# ESP32-ng.net
KiCad netlist of a schematic drawn in EAGLE
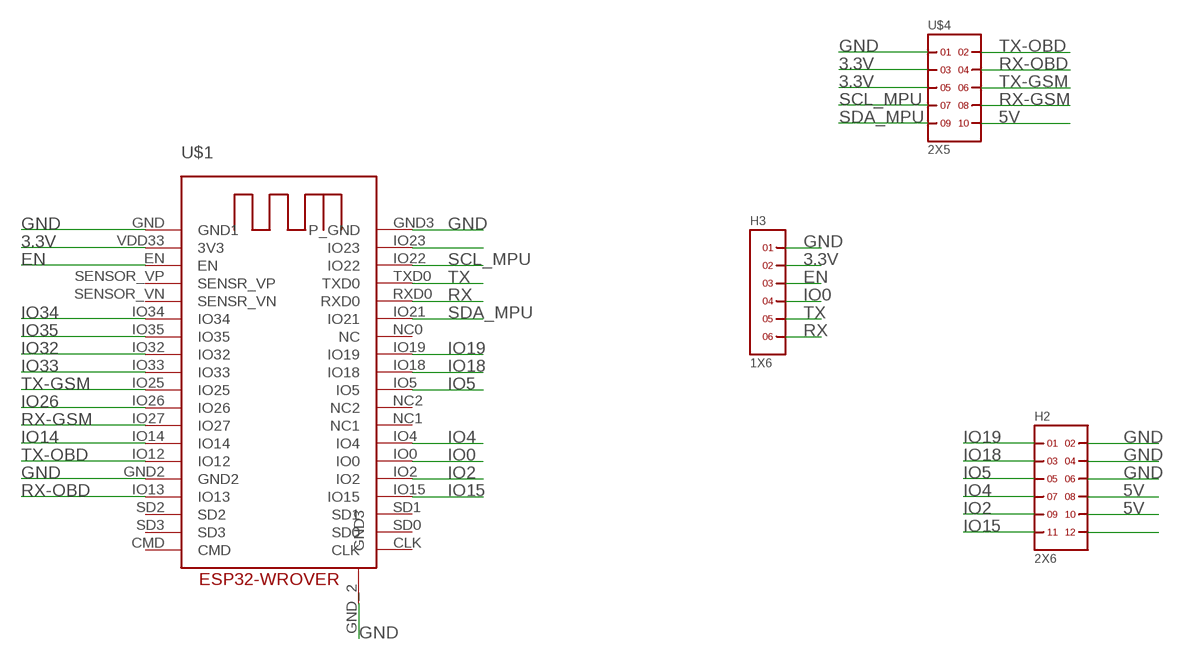
[diagram p0: schematic, sheet 1]

(export (version "E")
  (design (tool "Eeschema 10.0.6"))
  (components
    (comp (ref "H2")
      (value "2X6")
      (footprint "eagle-import:2X6")
      (libsource (lib "eagle-import") (part "2X6"))
    )
    (comp (ref "H3")
      (value "1X6")
      (footprint "eagle-import:1X6")
      (libsource (lib "eagle-import") (part "1X6"))
    )
    (comp (ref "U$1")
      (value "ESP32-WROVER")
      (footprint "eagle-import:ESP32-WROVER")
      (libsource (lib "eagle-import") (part "ESP32-WROVER"))
    )
    (comp (ref "U$4")
      (value "2X5")
      (footprint "eagle-import:2X5")
      (libsource (lib "eagle-import") (part "2X5"))
    )
  )
  (nets
    (net (code "1") (name "/3.3V") (class "Default")
      (node (ref "H3") (pin "2") (pinfunction "2_2") (pintype "bidirectional"))
      (node (ref "U$1") (pin "VDD33") (pinfunction "3V3_VDD33") (pintype "bidirectional"))
      (node (ref "U$4") (pin "3") (pinfunction "3_3") (pintype "bidirectional"))
      (node (ref "U$4") (pin "5") (pinfunction "5_5") (pintype "bidirectional"))
    )
    (net (code "2") (name "/5V") (class "Default")
      (node (ref "H2") (pin "10") (pinfunction "10_10") (pintype "bidirectional"))
      (node (ref "H2") (pin "8") (pinfunction "8_8") (pintype "bidirectional"))
      (node (ref "U$4") (pin "10") (pinfunction "10_10") (pintype "bidirectional"))
    )
    (net (code "3") (name "/EN") (class "Default")
      (node (ref "H3") (pin "3") (pinfunction "3_3") (pintype "bidirectional"))
      (node (ref "U$1") (pin "EN") (pinfunction "EN_EN") (pintype "bidirectional"))
    )
    (net (code "4") (name "/GND") (class "Default")
      (node (ref "H2") (pin "2") (pinfunction "2_2") (pintype "bidirectional"))
      (node (ref "H2") (pin "4") (pinfunction "4_4") (pintype "bidirectional"))
      (node (ref "H2") (pin "6") (pinfunction "6_6") (pintype "bidirectional"))
      (node (ref "H3") (pin "1") (pinfunction "1_1") (pintype "bidirectional"))
      (node (ref "U$1") (pin "GND") (pinfunction "GND1_GND") (pintype "bidirectional"))
      (node (ref "U$1") (pin "GND2") (pinfunction "GND2_GND2") (pintype "bidirectional"))
      (node (ref "U$1") (pin "GND3") (pinfunction "P_GND_GND3") (pintype "bidirectional"))
      (node (ref "U$1") (pin "GND_2") (pinfunction "GND3_GND_2") (pintype "bidirectional"))
      (node (ref "U$4") (pin "1") (pinfunction "1_1") (pintype "bidirectional"))
    )
    (net (code "5") (name "/IO0") (class "Default")
      (node (ref "H3") (pin "4") (pinfunction "4_4") (pintype "bidirectional"))
      (node (ref "U$1") (pin "IO0") (pinfunction "IO0_IO0") (pintype "bidirectional"))
    )
    (net (code "6") (name "/IO2") (class "Default")
      (node (ref "H2") (pin "9") (pinfunction "9_9") (pintype "bidirectional"))
      (node (ref "U$1") (pin "IO2") (pinfunction "IO2_IO2") (pintype "bidirectional"))
    )
    (net (code "7") (name "/IO4") (class "Default")
      (node (ref "H2") (pin "7") (pinfunction "7_7") (pintype "bidirectional"))
      (node (ref "U$1") (pin "IO4") (pinfunction "IO4_IO4") (pintype "bidirectional"))
    )
    (net (code "8") (name "/IO5") (class "Default")
      (node (ref "H2") (pin "5") (pinfunction "5_5") (pintype "bidirectional"))
      (node (ref "U$1") (pin "IO5") (pinfunction "IO5_IO5") (pintype "bidirectional"))
    )
    (net (code "9") (name "/IO14") (class "Default")
      (node (ref "U$1") (pin "IO14") (pinfunction "IO14_IO14") (pintype "bidirectional"))
    )
    (net (code "10") (name "/IO15") (class "Default")
      (node (ref "H2") (pin "11") (pinfunction "11_11") (pintype "bidirectional"))
      (node (ref "U$1") (pin "IO15") (pinfunction "IO15_IO15") (pintype "bidirectional"))
    )
    (net (code "11") (name "/IO18") (class "Default")
      (node (ref "H2") (pin "3") (pinfunction "3_3") (pintype "bidirectional"))
      (node (ref "U$1") (pin "IO18") (pinfunction "IO18_IO18") (pintype "bidirectional"))
    )
    (net (code "12") (name "/IO19") (class "Default")
      (node (ref "H2") (pin "1") (pinfunction "1_1") (pintype "bidirectional"))
      (node (ref "U$1") (pin "IO19") (pinfunction "IO19_IO19") (pintype "bidirectional"))
    )
    (net (code "13") (name "/IO26") (class "Default")
      (node (ref "U$1") (pin "IO26") (pinfunction "IO26_IO26") (pintype "bidirectional"))
    )
    (net (code "14") (name "/IO32") (class "Default")
      (node (ref "U$1") (pin "IO32") (pinfunction "IO32_IO32") (pintype "bidirectional"))
    )
    (net (code "15") (name "/IO33") (class "Default")
      (node (ref "U$1") (pin "IO33") (pinfunction "IO33_IO33") (pintype "bidirectional"))
    )
    (net (code "16") (name "/IO34") (class "Default")
      (node (ref "U$1") (pin "IO34") (pinfunction "IO34_IO34") (pintype "bidirectional"))
    )
    (net (code "17") (name "/IO35") (class "Default")
      (node (ref "U$1") (pin "IO35") (pinfunction "IO35_IO35") (pintype "bidirectional"))
    )
    (net (code "18") (name "/RX") (class "Default")
      (node (ref "H3") (pin "6") (pinfunction "6_6") (pintype "bidirectional"))
      (node (ref "U$1") (pin "RXD0") (pinfunction "RXD0_RXD0") (pintype "bidirectional"))
    )
    (net (code "19") (name "/RX-GSM") (class "Default")
      (node (ref "U$1") (pin "IO27") (pinfunction "IO27_IO27") (pintype "bidirectional"))
      (node (ref "U$4") (pin "8") (pinfunction "8_8") (pintype "bidirectional"))
    )
    (net (code "20") (name "/RX-OBD") (class "Default")
      (node (ref "U$1") (pin "IO13") (pinfunction "IO13_IO13") (pintype "bidirectional"))
      (node (ref "U$4") (pin "4") (pinfunction "4_4") (pintype "bidirectional"))
    )
    (net (code "21") (name "/SCL_MPU") (class "Default")
      (node (ref "U$1") (pin "IO22") (pinfunction "IO22_IO22") (pintype "bidirectional"))
      (node (ref "U$4") (pin "7") (pinfunction "7_7") (pintype "bidirectional"))
    )
    (net (code "22") (name "/SDA_MPU") (class "Default")
      (node (ref "U$1") (pin "IO21") (pinfunction "IO21_IO21") (pintype "bidirectional"))
      (node (ref "U$4") (pin "9") (pinfunction "9_9") (pintype "bidirectional"))
    )
    (net (code "23") (name "/TX") (class "Default")
      (node (ref "H3") (pin "5") (pinfunction "5_5") (pintype "bidirectional"))
      (node (ref "U$1") (pin "TXD0") (pinfunction "TXD0_TXD0") (pintype "bidirectional"))
    )
    (net (code "24") (name "/TX-GSM") (class "Default")
      (node (ref "U$1") (pin "IO25") (pinfunction "IO25_IO25") (pintype "bidirectional"))
      (node (ref "U$4") (pin "6") (pinfunction "6_6") (pintype "bidirectional"))
    )
    (net (code "25") (name "/TX-OBD") (class "Default")
      (node (ref "U$1") (pin "IO12") (pinfunction "IO12_IO12") (pintype "bidirectional"))
      (node (ref "U$4") (pin "2") (pinfunction "2_2") (pintype "bidirectional"))
    )
    (net (code "26") (name "unconnected-(H2-Pad12)") (class "Default")
      (node (ref "H2") (pin "12") (pinfunction "12_12") (pintype "bidirectional"))
    )
    (net (code "27") (name "unconnected-(U$1-NC-PadNC0)") (class "Default")
      (node (ref "U$1") (pin "NC0") (pinfunction "NC_NC0") (pintype "bidirectional"))
    )
    (net (code "28") (name "unconnected-(U$1-PadCLK)") (class "Default")
      (node (ref "U$1") (pin "CLK") (pinfunction "CLK_CLK") (pintype "bidirectional"))
    )
    (net (code "29") (name "unconnected-(U$1-PadCMD)") (class "Default")
      (node (ref "U$1") (pin "CMD") (pinfunction "CMD_CMD") (pintype "bidirectional"))
    )
    (net (code "30") (name "unconnected-(U$1-PadIO23)") (class "Default")
      (node (ref "U$1") (pin "IO23") (pinfunction "IO23_IO23") (pintype "bidirectional"))
    )
    (net (code "31") (name "unconnected-(U$1-PadNC1)") (class "Default")
      (node (ref "U$1") (pin "NC1") (pinfunction "NC1_NC1") (pintype "bidirectional"))
    )
    (net (code "32") (name "unconnected-(U$1-PadNC2)") (class "Default")
      (node (ref "U$1") (pin "NC2") (pinfunction "NC2_NC2") (pintype "bidirectional"))
    )
    (net (code "33") (name "unconnected-(U$1-PadSD0)") (class "Default")
      (node (ref "U$1") (pin "SD0") (pinfunction "SD0_SD0") (pintype "bidirectional"))
    )
    (net (code "34") (name "unconnected-(U$1-PadSD1)") (class "Default")
      (node (ref "U$1") (pin "SD1") (pinfunction "SD1_SD1") (pintype "bidirectional"))
    )
    (net (code "35") (name "unconnected-(U$1-PadSD2)") (class "Default")
      (node (ref "U$1") (pin "SD2") (pinfunction "SD2_SD2") (pintype "bidirectional"))
    )
    (net (code "36") (name "unconnected-(U$1-PadSD3)") (class "Default")
      (node (ref "U$1") (pin "SD3") (pinfunction "SD3_SD3") (pintype "bidirectional"))
    )
    (net (code "37") (name "unconnected-(U$1-SENSR_VN-PadSENSOR_VN)") (class "Default")
      (node (ref "U$1") (pin "SENSOR_VN") (pinfunction "SENSR_VN_SENSOR_VN") (pintype "bidirectional"))
    )
    (net (code "38") (name "unconnected-(U$1-SENSR_VP-PadSENSOR_VP)") (class "Default")
      (node (ref "U$1") (pin "SENSOR_VP") (pinfunction "SENSR_VP_SENSOR_VP") (pintype "bidirectional"))
    )
  )
)
